# PowerSupp.net
KiCad netlist of a schematic drawn in Altium Designer
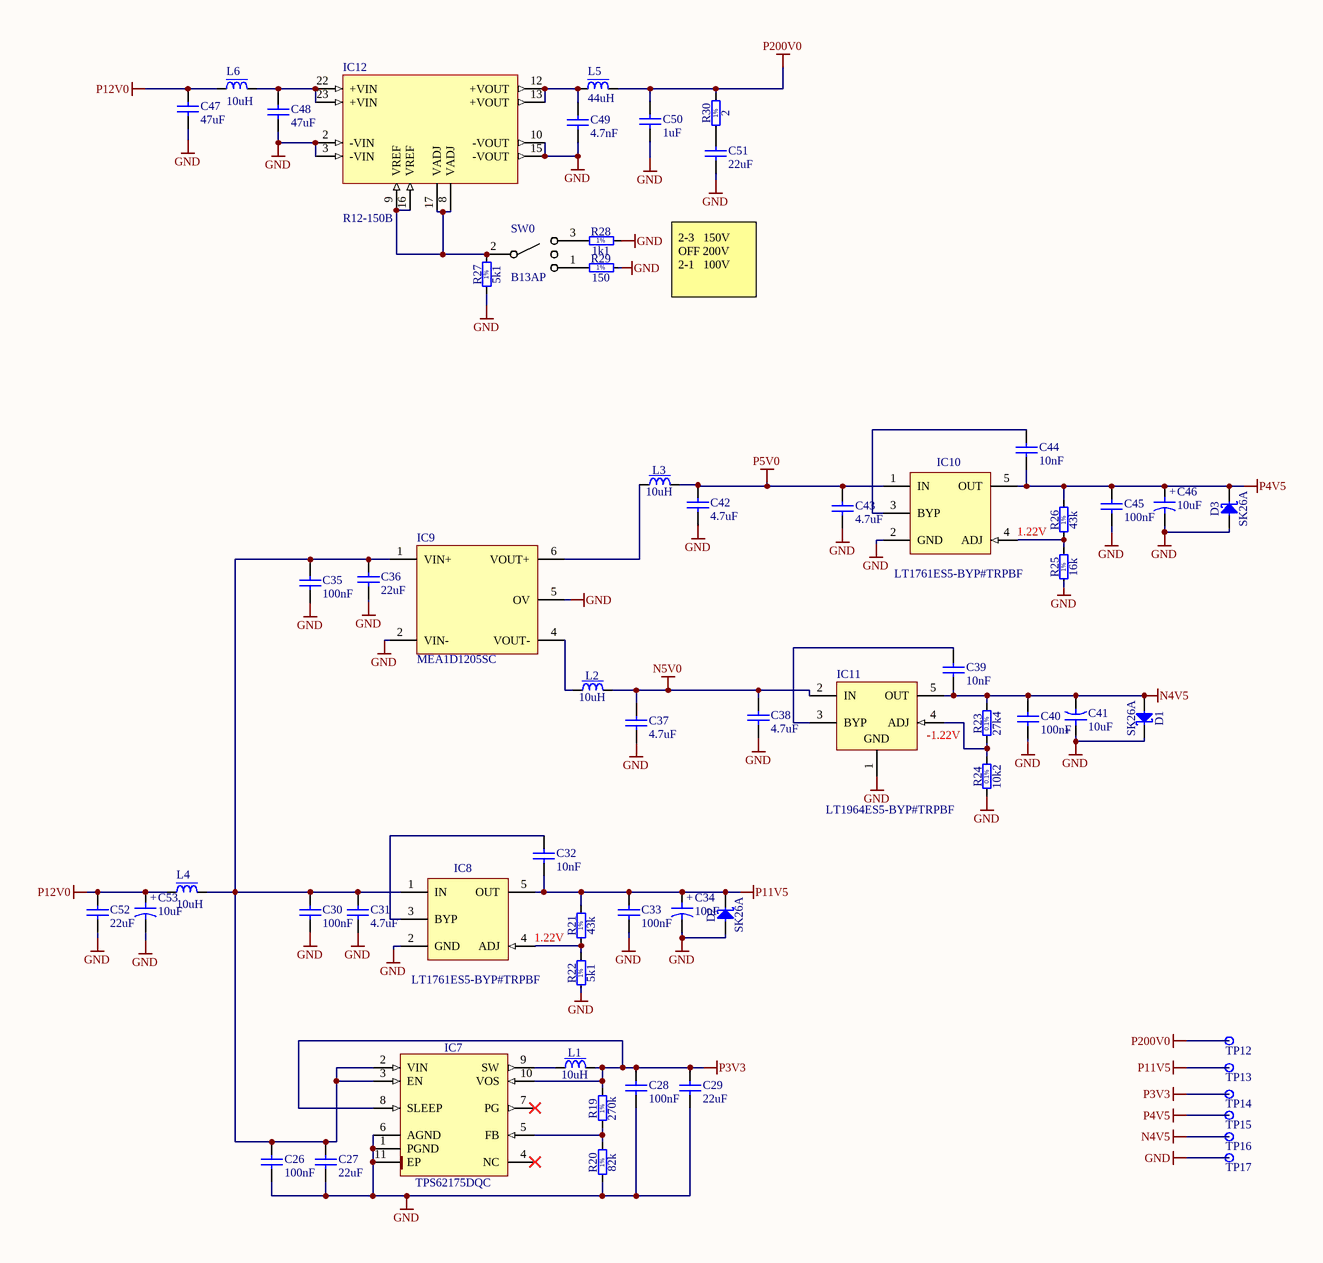
[diagram p0: PowerSupp.SchDoc]

(export (version "E")
  (design (tool "Eeschema 10.0.6"))
  (components
    (comp (ref "C26")
      (value "100nF")
      (footprint "C0402C104K4RACTU")
      (description "Capacitor; Ceramic; Cap; .100uF; Tol 10%; SMT; Vol-Rtg 16V; X7R; Tape and Reel")
      (fields (field (name "TOLERANCE") "10%"))
      (libsource (lib "CapacitorLibrary") (part "C0402C104K4RACTU"))
    )
    (comp (ref "C27")
      (value "22uF")
      (footprint "GRM219R61C226ME15K")
      (description "CAP CER 22uF 16V X5R 20% SMD 0805 85°C Embossed T/R")
      (fields (field (name "TOLERANCE") "20%"))
      (libsource (lib "CapacitorLibrary") (part "GRM219R61C226ME15K"))
    )
    (comp (ref "C28")
      (value "100nF")
      (footprint "C0402C104K4RACTU")
      (description "Capacitor; Ceramic; Cap; .100uF; Tol 10%; SMT; Vol-Rtg 16V; X7R; Tape and Reel")
      (fields (field (name "TOLERANCE") "10%"))
      (libsource (lib "CapacitorLibrary") (part "C0402C104K4RACTU"))
    )
    (comp (ref "C29")
      (value "22uF")
      (footprint "GRM219R61C226ME15K")
      (description "CAP CER 22uF 16V X5R 20% SMD 0805 85°C Embossed T/R")
      (fields (field (name "TOLERANCE") "20%"))
      (libsource (lib "CapacitorLibrary") (part "GRM219R61C226ME15K"))
    )
    (comp (ref "C30")
      (value "100nF")
      (footprint "C0402C104K4RACTU")
      (description "Capacitor; Ceramic; Cap; .100uF; Tol 10%; SMT; Vol-Rtg 16V; X7R; Tape and Reel")
      (fields (field (name "TOLERANCE") "10%"))
      (libsource (lib "CapacitorLibrary") (part "C0402C104K4RACTU"))
    )
    (comp (ref "C31")
      (value "4.7uF")
      (footprint "C0805C475K4RACTU")
      (description "CAP CER 4.7uF 16V X7R 10% Pad SMD 0805 125C T/R")
      (fields (field (name "TOLERANCE") "10%") (field (name "VOLTAGE") "16V"))
      (libsource (lib "CapacitorLibrary") (part "C0805C475K4RACTU"))
    )
    (comp (ref "C32")
      (value "10nF")
      (footprint "C0402C103K4RACTU")
      (description "CAP CER 10nF 16V X7R 10% SMD 0402 125C Paper T/R")
      (fields (field (name "TOLERANCE") "10%") (field (name "VOLTAGE") "16V"))
      (libsource (lib "CapacitorLibrary") (part "C0402C103K4RACTU"))
    )
    (comp (ref "C33")
      (value "100nF")
      (footprint "C0402C104K4RACTU")
      (description "Capacitor; Ceramic; Cap; .100uF; Tol 10%; SMT; Vol-Rtg 16V; X7R; Tape and Reel")
      (fields (field (name "TOLERANCE") "10%"))
      (libsource (lib "CapacitorLibrary") (part "C0402C104K4RACTU"))
    )
    (comp (ref "C34")
      (value "10uF")
      (footprint "TCJT106M016R0200")
      (description "CAP TANT POLY 10UF 16V 1210")
      (fields (field (name "TOLERANCE") "20%") (field (name "VOLTAGE") "16V"))
      (libsource (lib "CapacitorLibrary") (part "TCJT106M016R0200"))
    )
    (comp (ref "C35")
      (value "100nF")
      (footprint "C0402C104K4RACTU")
      (description "Capacitor; Ceramic; Cap; .100uF; Tol 10%; SMT; Vol-Rtg 16V; X7R; Tape and Reel")
      (fields (field (name "TOLERANCE") "10%"))
      (libsource (lib "CapacitorLibrary") (part "C0402C104K4RACTU"))
    )
    (comp (ref "C36")
      (value "22uF")
      (footprint "GRM219R61C226ME15K")
      (description "CAP CER 22uF 16V X5R 20% SMD 0805 85°C Embossed T/R")
      (fields (field (name "TOLERANCE") "20%"))
      (libsource (lib "CapacitorLibrary") (part "GRM219R61C226ME15K"))
    )
    (comp (ref "C37")
      (value "4.7uF")
      (footprint "C0805C475K4RACTU")
      (description "CAP CER 4.7uF 16V X7R 10% Pad SMD 0805 125C T/R")
      (fields (field (name "TOLERANCE") "10%") (field (name "VOLTAGE") "16V"))
      (libsource (lib "CapacitorLibrary") (part "C0805C475K4RACTU"))
    )
    (comp (ref "C38")
      (value "4.7uF")
      (footprint "C0805C475K4RACTU")
      (description "CAP CER 4.7uF 16V X7R 10% Pad SMD 0805 125C T/R")
      (fields (field (name "TOLERANCE") "10%") (field (name "VOLTAGE") "16V"))
      (libsource (lib "CapacitorLibrary") (part "C0805C475K4RACTU"))
    )
    (comp (ref "C39")
      (value "10nF")
      (footprint "C0402C103K4RACTU")
      (description "CAP CER 10nF 16V X7R 10% SMD 0402 125C Paper T/R")
      (fields (field (name "TOLERANCE") "10%") (field (name "VOLTAGE") "16V"))
      (libsource (lib "CapacitorLibrary") (part "C0402C103K4RACTU"))
    )
    (comp (ref "C40")
      (value "100nF")
      (footprint "C0402C104K4RACTU")
      (description "Capacitor; Ceramic; Cap; .100uF; Tol 10%; SMT; Vol-Rtg 16V; X7R; Tape and Reel")
      (fields (field (name "TOLERANCE") "10%"))
      (libsource (lib "CapacitorLibrary") (part "C0402C104K4RACTU"))
    )
    (comp (ref "C41")
      (value "10uF")
      (footprint "TCJT106M016R0200")
      (description "CAP TANT POLY 10UF 16V 1210")
      (fields (field (name "TOLERANCE") "20%") (field (name "VOLTAGE") "16V"))
      (libsource (lib "CapacitorLibrary") (part "TCJT106M016R0200"))
    )
    (comp (ref "C42")
      (value "4.7uF")
      (footprint "C0805C475K4RACTU")
      (description "CAP CER 4.7uF 16V X7R 10% Pad SMD 0805 125C T/R")
      (fields (field (name "TOLERANCE") "10%") (field (name "VOLTAGE") "16V"))
      (libsource (lib "CapacitorLibrary") (part "C0805C475K4RACTU"))
    )
    (comp (ref "C43")
      (value "4.7uF")
      (footprint "C0805C475K4RACTU")
      (description "CAP CER 4.7uF 16V X7R 10% Pad SMD 0805 125C T/R")
      (fields (field (name "TOLERANCE") "10%") (field (name "VOLTAGE") "16V"))
      (libsource (lib "CapacitorLibrary") (part "C0805C475K4RACTU"))
    )
    (comp (ref "C44")
      (value "10nF")
      (footprint "C0402C103K4RACTU")
      (description "CAP CER 10nF 16V X7R 10% SMD 0402 125C Paper T/R")
      (fields (field (name "TOLERANCE") "10%") (field (name "VOLTAGE") "16V"))
      (libsource (lib "CapacitorLibrary") (part "C0402C103K4RACTU"))
    )
    (comp (ref "C45")
      (value "100nF")
      (footprint "C0402C104K4RACTU")
      (description "Capacitor; Ceramic; Cap; .100uF; Tol 10%; SMT; Vol-Rtg 16V; X7R; Tape and Reel")
      (fields (field (name "TOLERANCE") "10%"))
      (libsource (lib "CapacitorLibrary") (part "C0402C104K4RACTU"))
    )
    (comp (ref "C46")
      (value "10uF")
      (footprint "TCJT106M016R0200")
      (description "CAP TANT POLY 10UF 16V 1210")
      (fields (field (name "TOLERANCE") "20%") (field (name "VOLTAGE") "16V"))
      (libsource (lib "CapacitorLibrary") (part "TCJT106M016R0200"))
    )
    (comp (ref "C47")
      (value "47uF")
      (footprint "C5750X7R1C476M230KB")
      (description "CAP CER 47 F, 16 V,  20%, X7R, C Series, 2220 [5650 Metric]")
      (fields (field (name "TOLERANCE") "20%") (field (name "VOLTAGE") "16V"))
      (libsource (lib "CapacitorLibrary") (part "C5750X7R1C476M230KB"))
    )
    (comp (ref "C48")
      (value "47uF")
      (footprint "C5750X7R1C476M230KB")
      (description "CAP CER 47 F, 16 V,  20%, X7R, C Series, 2220 [5650 Metric]")
      (fields (field (name "TOLERANCE") "20%") (field (name "VOLTAGE") "16V"))
      (libsource (lib "CapacitorLibrary") (part "C5750X7R1C476M230KB"))
    )
    (comp (ref "C49")
      (value "4.7nF")
      (footprint "CC0805KRX7RYBB472")
      (description "CAP CER 4700PF 250V X7R 0805")
      (fields (field (name "TOLERANCE") "10%"))
      (libsource (lib "CapacitorLibrary") (part "CC0805KRX7RYBB472"))
    )
    (comp (ref "C50")
      (value "1uF")
      (footprint "GC355XD72E105KX05L")
      (description "CAP CER 1UF 250V X7T 2220")
      (fields (field (name "TOLERANCE") "10%"))
      (libsource (lib "CapacitorLibrary") (part "GC355XD72E105KX05L"))
    )
    (comp (ref "C51")
      (value "22uF")
      (footprint "R60IR52205000K")
      (description "CAP FILM, PET, 22UF, 250V, RADIAL")
      (fields (field (name "MANUFACTURER_PART_NUMBER") "R60IR52205000K") (field (name "TOLERANCE") "10%"))
      (libsource (lib "CapacitorLibrary") (part "R60IR52205000K"))
    )
    (comp (ref "C52")
      (value "22uF")
      (footprint "GRM219R61C226ME15K")
      (description "CAP CER 22uF 16V X5R 20% SMD 0805 85°C Embossed T/R")
      (fields (field (name "TOLERANCE") "20%"))
      (libsource (lib "CapacitorLibrary") (part "GRM219R61C226ME15K"))
    )
    (comp (ref "C53")
      (value "10uF")
      (footprint "TCJT106M016R0200")
      (description "CAP TANT POLY 10UF 16V 1210")
      (fields (field (name "TOLERANCE") "20%") (field (name "VOLTAGE") "16V"))
      (libsource (lib "CapacitorLibrary") (part "TCJT106M016R0200"))
    )
    (comp (ref "D1")
      (value "SK26A")
      (footprint "DIOM5126X265N")
      (description "Schottky Diode")
      (fields
        (field (name "VOLTAGE") "60V")
        (field (name "POWER") "2A")
        (field (name "AUTHOR") "CERN DEM JMW")
      )
      (libsource (lib "ICs And Semiconductors") (part "Diode Schottky"))
    )
    (comp (ref "D2")
      (value "SK26A")
      (footprint "DIOM5126X265N")
      (description "Schottky Diode")
      (fields
        (field (name "VOLTAGE") "60V")
        (field (name "POWER") "2A")
        (field (name "AUTHOR") "CERN DEM JMW")
      )
      (libsource (lib "ICs And Semiconductors") (part "Diode Schottky"))
    )
    (comp (ref "D3")
      (value "SK26A")
      (footprint "DIOM5126X265N")
      (description "Schottky Diode")
      (fields
        (field (name "VOLTAGE") "60V")
        (field (name "POWER") "2A")
        (field (name "AUTHOR") "CERN DEM JMW")
      )
      (libsource (lib "ICs And Semiconductors") (part "Diode Schottky"))
    )
    (comp (ref "IC7")
      (value "TPS62175DQC")
      (footprint "SON50P200X300X80-11N-R94X250")
      (description "4.75-28VDC to 1-6VDC, 500mA Step-Down Converter With Sleep Mode")
      (fields (field (name "MANUFACTURER") "TEXAS INSTRUMENTS") (field (name "AUTHOR") "CERN DEM JMW"))
      (libsource (lib "ICs And Semiconductors") (part "TPS62175"))
    )
    (comp (ref "IC8")
      (value "LT1761ES5-BYP#TRPBF")
      (footprint "LT-S5-5-TSOT-23_L")
      (description "LDO Regulator Pos 1.22V to 20V 0.1A 5-Pin TSOT-23 T/R")
      (libsource (lib "InzLib") (part "LT1761ES5-BYP#TRPBF"))
    )
    (comp (ref "IC9")
      (value "MEA1D1205SC")
      (footprint "MURA-SIP-5_V")
      (description "Module DC-DC 2-OUT 5V/-5V 0.1A/-0.1A 1W 5-Pin SIP Tube")
      (libsource (lib "InzLib") (part "MEA1D1205SC"))
    )
    (comp (ref "IC10")
      (value "LT1761ES5-BYP#TRPBF")
      (footprint "LT-S5-5-TSOT-23_L")
      (description "LDO Regulator Pos 1.22V to 20V 0.1A 5-Pin TSOT-23 T/R")
      (libsource (lib "InzLib") (part "LT1761ES5-BYP#TRPBF"))
    )
    (comp (ref "IC11")
      (value "LT1964ES5-BYP#TRPBF")
      (footprint "LT-S5-5-TSOT-23_L")
      (description "IC REG LDO NEG ADJ 0.2A TSOT23-5")
      (libsource (lib "InzLib") (part "LT1964ES5-BYP#TRPBF"))
    )
    (comp (ref "IC12")
      (value "R12-150B")
      (footprint "CONV_R12-100B")
      (description "DC DC CONVERTER 95-210V 5W")
      (libsource (lib "InzLib") (part "R12-150B"))
    )
    (comp (ref "L1")
      (value "10uH")
      (footprint "IND_MURATA-PS_8400")
      (description "Inductor With Core")
      (fields
        (field (name "PART NUMBER") "IND_10UH_10%_MURATA-PS_8400")
        (field (name "POWER") "950mA")
        (field (name "AUTHOR") "CERN DEM JLC")
      )
      (libsource (lib "Inductors & Transformers") (part "Inductor With Magnetic core"))
    )
    (comp (ref "L2")
      (value "10uH")
      (footprint "IND_MURATA-PS_8400")
      (description "Inductor With Core")
      (fields
        (field (name "PART NUMBER") "IND_10UH_10%_MURATA-PS_8400")
        (field (name "POWER") "950mA")
        (field (name "AUTHOR") "CERN DEM JLC")
      )
      (libsource (lib "Inductors & Transformers") (part "Inductor With Magnetic core"))
    )
    (comp (ref "L3")
      (value "10uH")
      (footprint "IND_MURATA-PS_8400")
      (description "Inductor With Core")
      (fields
        (field (name "PART NUMBER") "IND_10UH_10%_MURATA-PS_8400")
        (field (name "POWER") "950mA")
        (field (name "AUTHOR") "CERN DEM JLC")
      )
      (libsource (lib "Inductors & Transformers") (part "Inductor With Magnetic core"))
    )
    (comp (ref "L4")
      (value "10uH")
      (footprint "IND_MURATA-PS_8400")
      (description "Inductor With Core")
      (fields
        (field (name "PART NUMBER") "IND_10UH_10%_MURATA-PS_8400")
        (field (name "POWER") "950mA")
        (field (name "AUTHOR") "CERN DEM JLC")
      )
      (libsource (lib "Inductors & Transformers") (part "Inductor With Magnetic core"))
    )
    (comp (ref "L5")
      (value "44uH")
      (footprint "LQH44PH100MPRL")
      (libsource (lib "InzLib") (part "LQH44PH470MPRL"))
    )
    (comp (ref "L6")
      (value "10uH")
      (footprint "IND_MURATA-PS_8400")
      (description "Inductor With Core")
      (fields
        (field (name "PART NUMBER") "IND_10UH_10%_MURATA-PS_8400")
        (field (name "POWER") "950mA")
        (field (name "AUTHOR") "CERN DEM JLC")
      )
      (libsource (lib "Inductors & Transformers") (part "Inductor With Magnetic core"))
    )
    (comp (ref "R19")
      (value "270k")
      (footprint "RESC1608X55N")
      (description "Resistor - 1%")
      (fields
        (field (name "PART NUMBER") "R0603_270K_1%_0.1W_100PPM")
        (field (name "POWER") "0.1W")
        (field (name "AUTHOR") "CERN DEM JLC")
      )
      (libsource (lib "Resistors") (part "Resistor - 1%"))
    )
    (comp (ref "R20")
      (value "82k")
      (footprint "RESC1608X55N")
      (description "Resistor - 1%")
      (fields
        (field (name "PART NUMBER") "R0603_82K_1%_0.1W_100PPM")
        (field (name "POWER") "0.1W")
        (field (name "AUTHOR") "CERN DEM JLC")
      )
      (libsource (lib "Resistors") (part "Resistor - 1%"))
    )
    (comp (ref "R21")
      (value "43k")
      (footprint "RESC1608X55N")
      (description "Resistor - 1%")
      (fields
        (field (name "PART NUMBER") "R0603_43K_1%_0.1W_100PPM")
        (field (name "POWER") "0.1W")
        (field (name "AUTHOR") "CERN DEM JLC")
      )
      (libsource (lib "Resistors") (part "Resistor - 1%"))
    )
    (comp (ref "R22")
      (value "5k1")
      (footprint "RESC1608X55N")
      (description "Resistor - 1%")
      (fields
        (field (name "PART NUMBER") "R0603_5K1_1%_0.1W_100PPM")
        (field (name "POWER") "0.1W")
        (field (name "AUTHOR") "CERN DEM JLC")
      )
      (libsource (lib "Resistors") (part "Resistor - 1%"))
    )
    (comp (ref "R23")
      (value "27k4")
      (footprint "RESC1608X55N")
      (description "Resistor - 0.1%")
      (fields
        (field (name "PART NUMBER") "R0603_27K4_0.1%_0.063W_10PPM")
        (field (name "POWER") "0.063W")
        (field (name "AUTHOR") "CERN DEM JLC")
      )
      (libsource (lib "Resistors") (part "Resistor - 0.1%"))
    )
    (comp (ref "R24")
      (value "10k2")
      (footprint "RESC1608X55N")
      (description "Resistor - 0.1%")
      (fields
        (field (name "PART NUMBER") "R0603_10K2_0.1%_0.063W_10PPM")
        (field (name "POWER") "0.063W")
        (field (name "AUTHOR") "CERN DEM JLC")
      )
      (libsource (lib "Resistors") (part "Resistor - 0.1%"))
    )
    (comp (ref "R25")
      (value "16k")
      (footprint "RESC1608X55N")
      (description "Resistor - 1%")
      (fields
        (field (name "PART NUMBER") "R0603_16K_1%_0.1W_100PPM")
        (field (name "POWER") "0.1W")
        (field (name "AUTHOR") "CERN DEM JLC")
      )
      (libsource (lib "Resistors") (part "Resistor - 1%"))
    )
    (comp (ref "R26")
      (value "43k")
      (footprint "RESC1608X55N")
      (description "Resistor - 1%")
      (fields
        (field (name "PART NUMBER") "R0603_43K_1%_0.1W_100PPM")
        (field (name "POWER") "0.1W")
        (field (name "AUTHOR") "CERN DEM JLC")
      )
      (libsource (lib "Resistors") (part "Resistor - 1%"))
    )
    (comp (ref "R27")
      (value "5k1")
      (footprint "RESC1608X55N")
      (description "Resistor - 1%")
      (fields
        (field (name "PART NUMBER") "R0603_5K1_1%_0.1W_100PPM")
        (field (name "POWER") "0.1W")
        (field (name "AUTHOR") "CERN DEM JLC")
      )
      (libsource (lib "Resistors") (part "Resistor - 1%"))
    )
    (comp (ref "R28")
      (value "1k1")
      (footprint "RESC1608X55N")
      (description "Resistor - 1%")
      (fields
        (field (name "PART NUMBER") "R0603_1K1_1%_0.1W_100PPM")
        (field (name "POWER") "0.1W")
        (field (name "AUTHOR") "CERN DEM JLC")
      )
      (libsource (lib "Resistors") (part "Resistor - 1%"))
    )
    (comp (ref "R29")
      (value "150")
      (footprint "RESC1608X55N")
      (description "Resistor - 1%")
      (fields
        (field (name "PART NUMBER") "R0603_150R_1%_0.1W_100PPM")
        (field (name "POWER") "0.1W")
        (field (name "AUTHOR") "CERN DEM JLC")
      )
      (libsource (lib "Resistors") (part "Resistor - 1%"))
    )
    (comp (ref "R30")
      (value "2")
      (footprint "RESC3216X65N")
      (description "Resistor - 1%")
      (fields
        (field (name "PART NUMBER") "R1206_2R_1%_0.25W_200PPM")
        (field (name "POWER") "0.25W")
        (field (name "AUTHOR") "CERN DEM JLC")
      )
      (libsource (lib "Resistors") (part "Resistor - 1%"))
    )
    (comp (ref "SW0")
      (value "B13AP")
      (footprint "B13AP")
      (description "Switch;  Sealed;  Anti-Static Toggle;  SPDT;  ON-OFF-ON;  Str PC;  No Cap;  0.4A;  28VAC/DC")
      (libsource (lib "InzLib") (part "B13AP"))
    )
    (comp (ref "TP12")
      (value "Test Point")
      (footprint "TPS127")
      (fields (field (name "PART NUMBER") "SMD_PAD_1.27X1.27MM") (field (name "AUTHOR") "CERN DEM JLC"))
      (libsource (lib "Eletro-mechanical") (part "Test Point"))
    )
    (comp (ref "TP13")
      (value "Test Point")
      (footprint "TPS127")
      (fields (field (name "PART NUMBER") "SMD_PAD_1.27X1.27MM") (field (name "AUTHOR") "CERN DEM JLC"))
      (libsource (lib "Eletro-mechanical") (part "Test Point"))
    )
    (comp (ref "TP14")
      (value "Test Point")
      (footprint "TPS127")
      (fields (field (name "PART NUMBER") "SMD_PAD_1.27X1.27MM") (field (name "AUTHOR") "CERN DEM JLC"))
      (libsource (lib "Eletro-mechanical") (part "Test Point"))
    )
    (comp (ref "TP15")
      (value "Test Point")
      (footprint "TPS127")
      (fields (field (name "PART NUMBER") "SMD_PAD_1.27X1.27MM") (field (name "AUTHOR") "CERN DEM JLC"))
      (libsource (lib "Eletro-mechanical") (part "Test Point"))
    )
    (comp (ref "TP16")
      (value "Test Point")
      (footprint "TPS127")
      (fields (field (name "PART NUMBER") "SMD_PAD_1.27X1.27MM") (field (name "AUTHOR") "CERN DEM JLC"))
      (libsource (lib "Eletro-mechanical") (part "Test Point"))
    )
    (comp (ref "TP17")
      (value "Test Point")
      (footprint "TPS127")
      (fields (field (name "PART NUMBER") "SMD_PAD_1.27X1.27MM") (field (name "AUTHOR") "CERN DEM JLC"))
      (libsource (lib "Eletro-mechanical") (part "Test Point"))
    )
  )
  (nets
    (net (code "1") (name "GND") (class "Default")
      (node (ref "C26") (pin "1") (pinfunction "1_1") (pintype "passive"))
      (node (ref "C27") (pin "1") (pinfunction "1_1") (pintype "passive"))
      (node (ref "C28") (pin "1") (pinfunction "1_1") (pintype "passive"))
      (node (ref "C29") (pin "1") (pinfunction "1_1") (pintype "passive"))
      (node (ref "C30") (pin "1") (pinfunction "1_1") (pintype "passive"))
      (node (ref "C31") (pin "1") (pinfunction "1_1") (pintype "passive"))
      (node (ref "C33") (pin "1") (pinfunction "1_1") (pintype "passive"))
      (node (ref "C34") (pin "2") (pinfunction "2_2") (pintype "passive"))
      (node (ref "C35") (pin "1") (pinfunction "1_1") (pintype "passive"))
      (node (ref "C36") (pin "1") (pinfunction "1_1") (pintype "passive"))
      (node (ref "C37") (pin "1") (pinfunction "1_1") (pintype "passive"))
      (node (ref "C38") (pin "1") (pinfunction "1_1") (pintype "passive"))
      (node (ref "C40") (pin "1") (pinfunction "1_1") (pintype "passive"))
      (node (ref "C41") (pin "1") (pinfunction "1_1") (pintype "passive"))
      (node (ref "C42") (pin "1") (pinfunction "1_1") (pintype "passive"))
      (node (ref "C43") (pin "1") (pinfunction "1_1") (pintype "passive"))
      (node (ref "C45") (pin "1") (pinfunction "1_1") (pintype "passive"))
      (node (ref "C46") (pin "2") (pinfunction "2_2") (pintype "passive"))
      (node (ref "C47") (pin "1") (pinfunction "1_1") (pintype "passive"))
      (node (ref "C48") (pin "1") (pinfunction "1_1") (pintype "passive"))
      (node (ref "C49") (pin "1") (pinfunction "1_1") (pintype "passive"))
      (node (ref "C50") (pin "1") (pinfunction "1_1") (pintype "passive"))
      (node (ref "C51") (pin "1") (pinfunction "1_1") (pintype "passive"))
      (node (ref "C52") (pin "1") (pinfunction "1_1") (pintype "passive"))
      (node (ref "C53") (pin "2") (pinfunction "2_2") (pintype "passive"))
      (node (ref "D1") (pin "1") (pinfunction "C_1") (pintype "passive"))
      (node (ref "D2") (pin "2") (pinfunction "A_2") (pintype "passive"))
      (node (ref "D3") (pin "2") (pinfunction "A_2") (pintype "passive"))
      (node (ref "IC10") (pin "2") (pinfunction "GND_2") (pintype "power_in"))
      (node (ref "IC11") (pin "1") (pinfunction "GND_1") (pintype "power_in"))
      (node (ref "IC12") (pin "10") (pinfunction "-VOUT_10") (pintype "output"))
      (node (ref "IC12") (pin "15") (pinfunction "-VOUT_15") (pintype "output"))
      (node (ref "IC12") (pin "2") (pinfunction "-VIN_2") (pintype "input"))
      (node (ref "IC12") (pin "3") (pinfunction "-VIN_3") (pintype "input"))
      (node (ref "IC7") (pin "1") (pinfunction "PGND_1") (pintype "power_in"))
      (node (ref "IC7") (pin "11") (pinfunction "EP_11") (pintype "power_in"))
      (node (ref "IC7") (pin "6") (pinfunction "AGND_6") (pintype "power_in"))
      (node (ref "IC8") (pin "2") (pinfunction "GND_2") (pintype "power_in"))
      (node (ref "IC9") (pin "2") (pinfunction "VIN-_2") (pintype "power_in"))
      (node (ref "IC9") (pin "5") (pinfunction "OV_5") (pintype "power_in"))
      (node (ref "R20") (pin "1") (pinfunction "1_1") (pintype "passive"))
      (node (ref "R22") (pin "1") (pinfunction "1_1") (pintype "passive"))
      (node (ref "R24") (pin "1") (pinfunction "1_1") (pintype "passive"))
      (node (ref "R25") (pin "1") (pinfunction "1_1") (pintype "passive"))
      (node (ref "R27") (pin "1") (pinfunction "1_1") (pintype "passive"))
      (node (ref "R28") (pin "2") (pinfunction "2_2") (pintype "passive"))
      (node (ref "R29") (pin "2") (pinfunction "2_2") (pintype "passive"))
      (node (ref "TP17") (pin "1") (pinfunction "1_1") (pintype "bidirectional"))
    )
    (net (code "2") (name "N4V5") (class "Default")
      (node (ref "C39") (pin "1") (pinfunction "1_1") (pintype "passive"))
      (node (ref "C40") (pin "2") (pinfunction "2_2") (pintype "passive"))
      (node (ref "C41") (pin "2") (pinfunction "2_2") (pintype "passive"))
      (node (ref "D1") (pin "2") (pinfunction "A_2") (pintype "passive"))
      (node (ref "IC11") (pin "5") (pinfunction "OUT_5") (pintype "power_in"))
      (node (ref "R23") (pin "2") (pinfunction "2_2") (pintype "passive"))
      (node (ref "TP16") (pin "1") (pinfunction "1_1") (pintype "bidirectional"))
    )
    (net (code "3") (name "N5V0") (class "Default")
      (node (ref "C37") (pin "2") (pinfunction "2_2") (pintype "passive"))
      (node (ref "C38") (pin "2") (pinfunction "2_2") (pintype "passive"))
      (node (ref "IC11") (pin "2") (pinfunction "IN_2") (pintype "power_in"))
      (node (ref "L2") (pin "2") (pinfunction "2_2") (pintype "passive"))
    )
    (net (code "4") (name "Net-(C48-Pad2)") (class "Default")
      (node (ref "C48") (pin "2") (pinfunction "2_2") (pintype "passive"))
      (node (ref "IC12") (pin "22") (pinfunction "+VIN_22") (pintype "input"))
      (node (ref "IC12") (pin "23") (pinfunction "+VIN_23") (pintype "input"))
      (node (ref "L6") (pin "2") (pinfunction "2_2") (pintype "passive"))
    )
    (net (code "5") (name "Net-(C49-Pad2)") (class "Default")
      (node (ref "C49") (pin "2") (pinfunction "2_2") (pintype "passive"))
      (node (ref "IC12") (pin "12") (pinfunction "+VOUT_12") (pintype "output"))
      (node (ref "IC12") (pin "13") (pinfunction "+VOUT_13") (pintype "output"))
      (node (ref "L5") (pin "1") (pinfunction "1_1") (pintype "passive"))
    )
    (net (code "6") (name "Net-(C51-Pad2)") (class "Default")
      (node (ref "C51") (pin "2") (pinfunction "2_2") (pintype "passive"))
      (node (ref "R30") (pin "1") (pinfunction "1_1") (pintype "passive"))
    )
    (net (code "7") (name "Net-(IC7-EN)") (class "Default")
      (node (ref "C26") (pin "2") (pinfunction "2_2") (pintype "passive"))
      (node (ref "C27") (pin "2") (pinfunction "2_2") (pintype "passive"))
      (node (ref "C30") (pin "2") (pinfunction "2_2") (pintype "passive"))
      (node (ref "C31") (pin "2") (pinfunction "2_2") (pintype "passive"))
      (node (ref "C35") (pin "2") (pinfunction "2_2") (pintype "passive"))
      (node (ref "C36") (pin "2") (pinfunction "2_2") (pintype "passive"))
      (node (ref "IC7") (pin "2") (pinfunction "VIN_2") (pintype "input"))
      (node (ref "IC7") (pin "3") (pinfunction "EN_3") (pintype "input"))
      (node (ref "IC8") (pin "1") (pinfunction "IN_1") (pintype "power_in"))
      (node (ref "IC9") (pin "1") (pinfunction "VIN+_1") (pintype "power_in"))
      (node (ref "L4") (pin "2") (pinfunction "2_2") (pintype "passive"))
    )
    (net (code "8") (name "Net-(IC7-FB)") (class "Default")
      (node (ref "IC7") (pin "5") (pinfunction "FB_5") (pintype "input"))
      (node (ref "R19") (pin "1") (pinfunction "1_1") (pintype "passive"))
      (node (ref "R20") (pin "2") (pinfunction "2_2") (pintype "passive"))
    )
    (net (code "9") (name "Net-(IC7-SW)") (class "Default")
      (node (ref "IC7") (pin "9") (pinfunction "SW_9") (pintype "output"))
      (node (ref "L1") (pin "1") (pinfunction "1_1") (pintype "passive"))
    )
    (net (code "10") (name "Net-(IC8-ADJ)") (class "Default")
      (node (ref "IC8") (pin "4") (pinfunction "ADJ_4") (pintype "input"))
      (node (ref "R21") (pin "1") (pinfunction "1_1") (pintype "passive"))
      (node (ref "R22") (pin "2") (pinfunction "2_2") (pintype "passive"))
    )
    (net (code "11") (name "Net-(IC8-BYP)") (class "Default")
      (node (ref "C32") (pin "2") (pinfunction "2_2") (pintype "passive"))
      (node (ref "IC8") (pin "3") (pinfunction "BYP_3") (pintype "passive"))
    )
    (net (code "12") (name "Net-(IC9-VOUT+)") (class "Default")
      (node (ref "IC9") (pin "6") (pinfunction "VOUT+_6") (pintype "power_in"))
      (node (ref "L3") (pin "1") (pinfunction "1_1") (pintype "passive"))
    )
    (net (code "13") (name "Net-(IC9-VOUT-)") (class "Default")
      (node (ref "IC9") (pin "4") (pinfunction "VOUT-_4") (pintype "power_in"))
      (node (ref "L2") (pin "1") (pinfunction "1_1") (pintype "passive"))
    )
    (net (code "14") (name "Net-(IC10-ADJ)") (class "Default")
      (node (ref "IC10") (pin "4") (pinfunction "ADJ_4") (pintype "input"))
      (node (ref "R25") (pin "2") (pinfunction "2_2") (pintype "passive"))
      (node (ref "R26") (pin "1") (pinfunction "1_1") (pintype "passive"))
    )
    (net (code "15") (name "Net-(IC10-BYP)") (class "Default")
      (node (ref "C44") (pin "2") (pinfunction "2_2") (pintype "passive"))
      (node (ref "IC10") (pin "3") (pinfunction "BYP_3") (pintype "passive"))
    )
    (net (code "16") (name "Net-(IC11-ADJ)") (class "Default")
      (node (ref "IC11") (pin "4") (pinfunction "ADJ_4") (pintype "input"))
      (node (ref "R23") (pin "1") (pinfunction "1_1") (pintype "passive"))
      (node (ref "R24") (pin "2") (pinfunction "2_2") (pintype "passive"))
    )
    (net (code "17") (name "Net-(IC11-BYP)") (class "Default")
      (node (ref "C39") (pin "2") (pinfunction "2_2") (pintype "passive"))
      (node (ref "IC11") (pin "3") (pinfunction "BYP_3") (pintype "passive"))
    )
    (net (code "18") (name "Net-(SW0-C)") (class "Default")
      (node (ref "IC12") (pin "16") (pinfunction "VREF_16") (pintype "input"))
      (node (ref "IC12") (pin "17") (pinfunction "VADJ_17") (pintype "passive"))
      (node (ref "IC12") (pin "8") (pinfunction "VADJ_8") (pintype "passive"))
      (node (ref "IC12") (pin "9") (pinfunction "VREF_9") (pintype "input"))
      (node (ref "R27") (pin "2") (pinfunction "2_2") (pintype "passive"))
      (node (ref "SW0") (pin "2") (pinfunction "C_2") (pintype "passive"))
    )
    (net (code "19") (name "Net-(SW0-NC)") (class "Default")
      (node (ref "R28") (pin "1") (pinfunction "1_1") (pintype "passive"))
      (node (ref "SW0") (pin "3") (pinfunction "NC_3") (pintype "passive"))
    )
    (net (code "20") (name "Net-(SW0-NO)") (class "Default")
      (node (ref "R29") (pin "1") (pinfunction "1_1") (pintype "passive"))
      (node (ref "SW0") (pin "1") (pinfunction "NO_1") (pintype "passive"))
    )
    (net (code "21") (name "P3V3") (class "Default")
      (node (ref "C28") (pin "2") (pinfunction "2_2") (pintype "passive"))
      (node (ref "C29") (pin "2") (pinfunction "2_2") (pintype "passive"))
      (node (ref "IC7") (pin "10") (pinfunction "VOS_10") (pintype "input"))
      (node (ref "IC7") (pin "8") (pinfunction "SLEEP_8") (pintype "input"))
      (node (ref "L1") (pin "2") (pinfunction "2_2") (pintype "passive"))
      (node (ref "R19") (pin "2") (pinfunction "2_2") (pintype "passive"))
      (node (ref "TP14") (pin "1") (pinfunction "1_1") (pintype "bidirectional"))
    )
    (net (code "22") (name "P4V5") (class "Default")
      (node (ref "C44") (pin "1") (pinfunction "1_1") (pintype "passive"))
      (node (ref "C45") (pin "2") (pinfunction "2_2") (pintype "passive"))
      (node (ref "C46") (pin "1") (pinfunction "1_1") (pintype "passive"))
      (node (ref "D3") (pin "1") (pinfunction "C_1") (pintype "passive"))
      (node (ref "IC10") (pin "5") (pinfunction "OUT_5") (pintype "power_in"))
      (node (ref "R26") (pin "2") (pinfunction "2_2") (pintype "passive"))
      (node (ref "TP15") (pin "1") (pinfunction "1_1") (pintype "bidirectional"))
    )
    (net (code "23") (name "P5V0") (class "Default")
      (node (ref "C42") (pin "2") (pinfunction "2_2") (pintype "passive"))
      (node (ref "C43") (pin "2") (pinfunction "2_2") (pintype "passive"))
      (node (ref "IC10") (pin "1") (pinfunction "IN_1") (pintype "power_in"))
      (node (ref "L3") (pin "2") (pinfunction "2_2") (pintype "passive"))
    )
    (net (code "24") (name "P11V5") (class "Default")
      (node (ref "C32") (pin "1") (pinfunction "1_1") (pintype "passive"))
      (node (ref "C33") (pin "2") (pinfunction "2_2") (pintype "passive"))
      (node (ref "C34") (pin "1") (pinfunction "1_1") (pintype "passive"))
      (node (ref "D2") (pin "1") (pinfunction "C_1") (pintype "passive"))
      (node (ref "IC8") (pin "5") (pinfunction "OUT_5") (pintype "power_in"))
      (node (ref "R21") (pin "2") (pinfunction "2_2") (pintype "passive"))
      (node (ref "TP13") (pin "1") (pinfunction "1_1") (pintype "bidirectional"))
    )
    (net (code "25") (name "P12V0") (class "Default")
      (node (ref "C47") (pin "2") (pinfunction "2_2") (pintype "passive"))
      (node (ref "C52") (pin "2") (pinfunction "2_2") (pintype "passive"))
      (node (ref "C53") (pin "1") (pinfunction "1_1") (pintype "passive"))
      (node (ref "L4") (pin "1") (pinfunction "1_1") (pintype "passive"))
      (node (ref "L6") (pin "1") (pinfunction "1_1") (pintype "passive"))
    )
    (net (code "26") (name "P200V0") (class "Default")
      (node (ref "C50") (pin "2") (pinfunction "2_2") (pintype "passive"))
      (node (ref "L5") (pin "2") (pinfunction "2_2") (pintype "passive"))
      (node (ref "R30") (pin "2") (pinfunction "2_2") (pintype "passive"))
      (node (ref "TP12") (pin "1") (pinfunction "1_1") (pintype "bidirectional"))
    )
    (net (code "27") (name "unconnected-(IC7-NC-Pad4)") (class "Default")
      (node (ref "IC7") (pin "4") (pinfunction "NC_4") (pintype "passive+no_connect"))
    )
    (net (code "28") (name "unconnected-(IC7-PG-Pad7)") (class "Default")
      (node (ref "IC7") (pin "7") (pinfunction "PG_7") (pintype "output+no_connect"))
    )
  )
)
